# DE-100224_01.net
KiCad netlist of a schematic drawn in Altium Designer
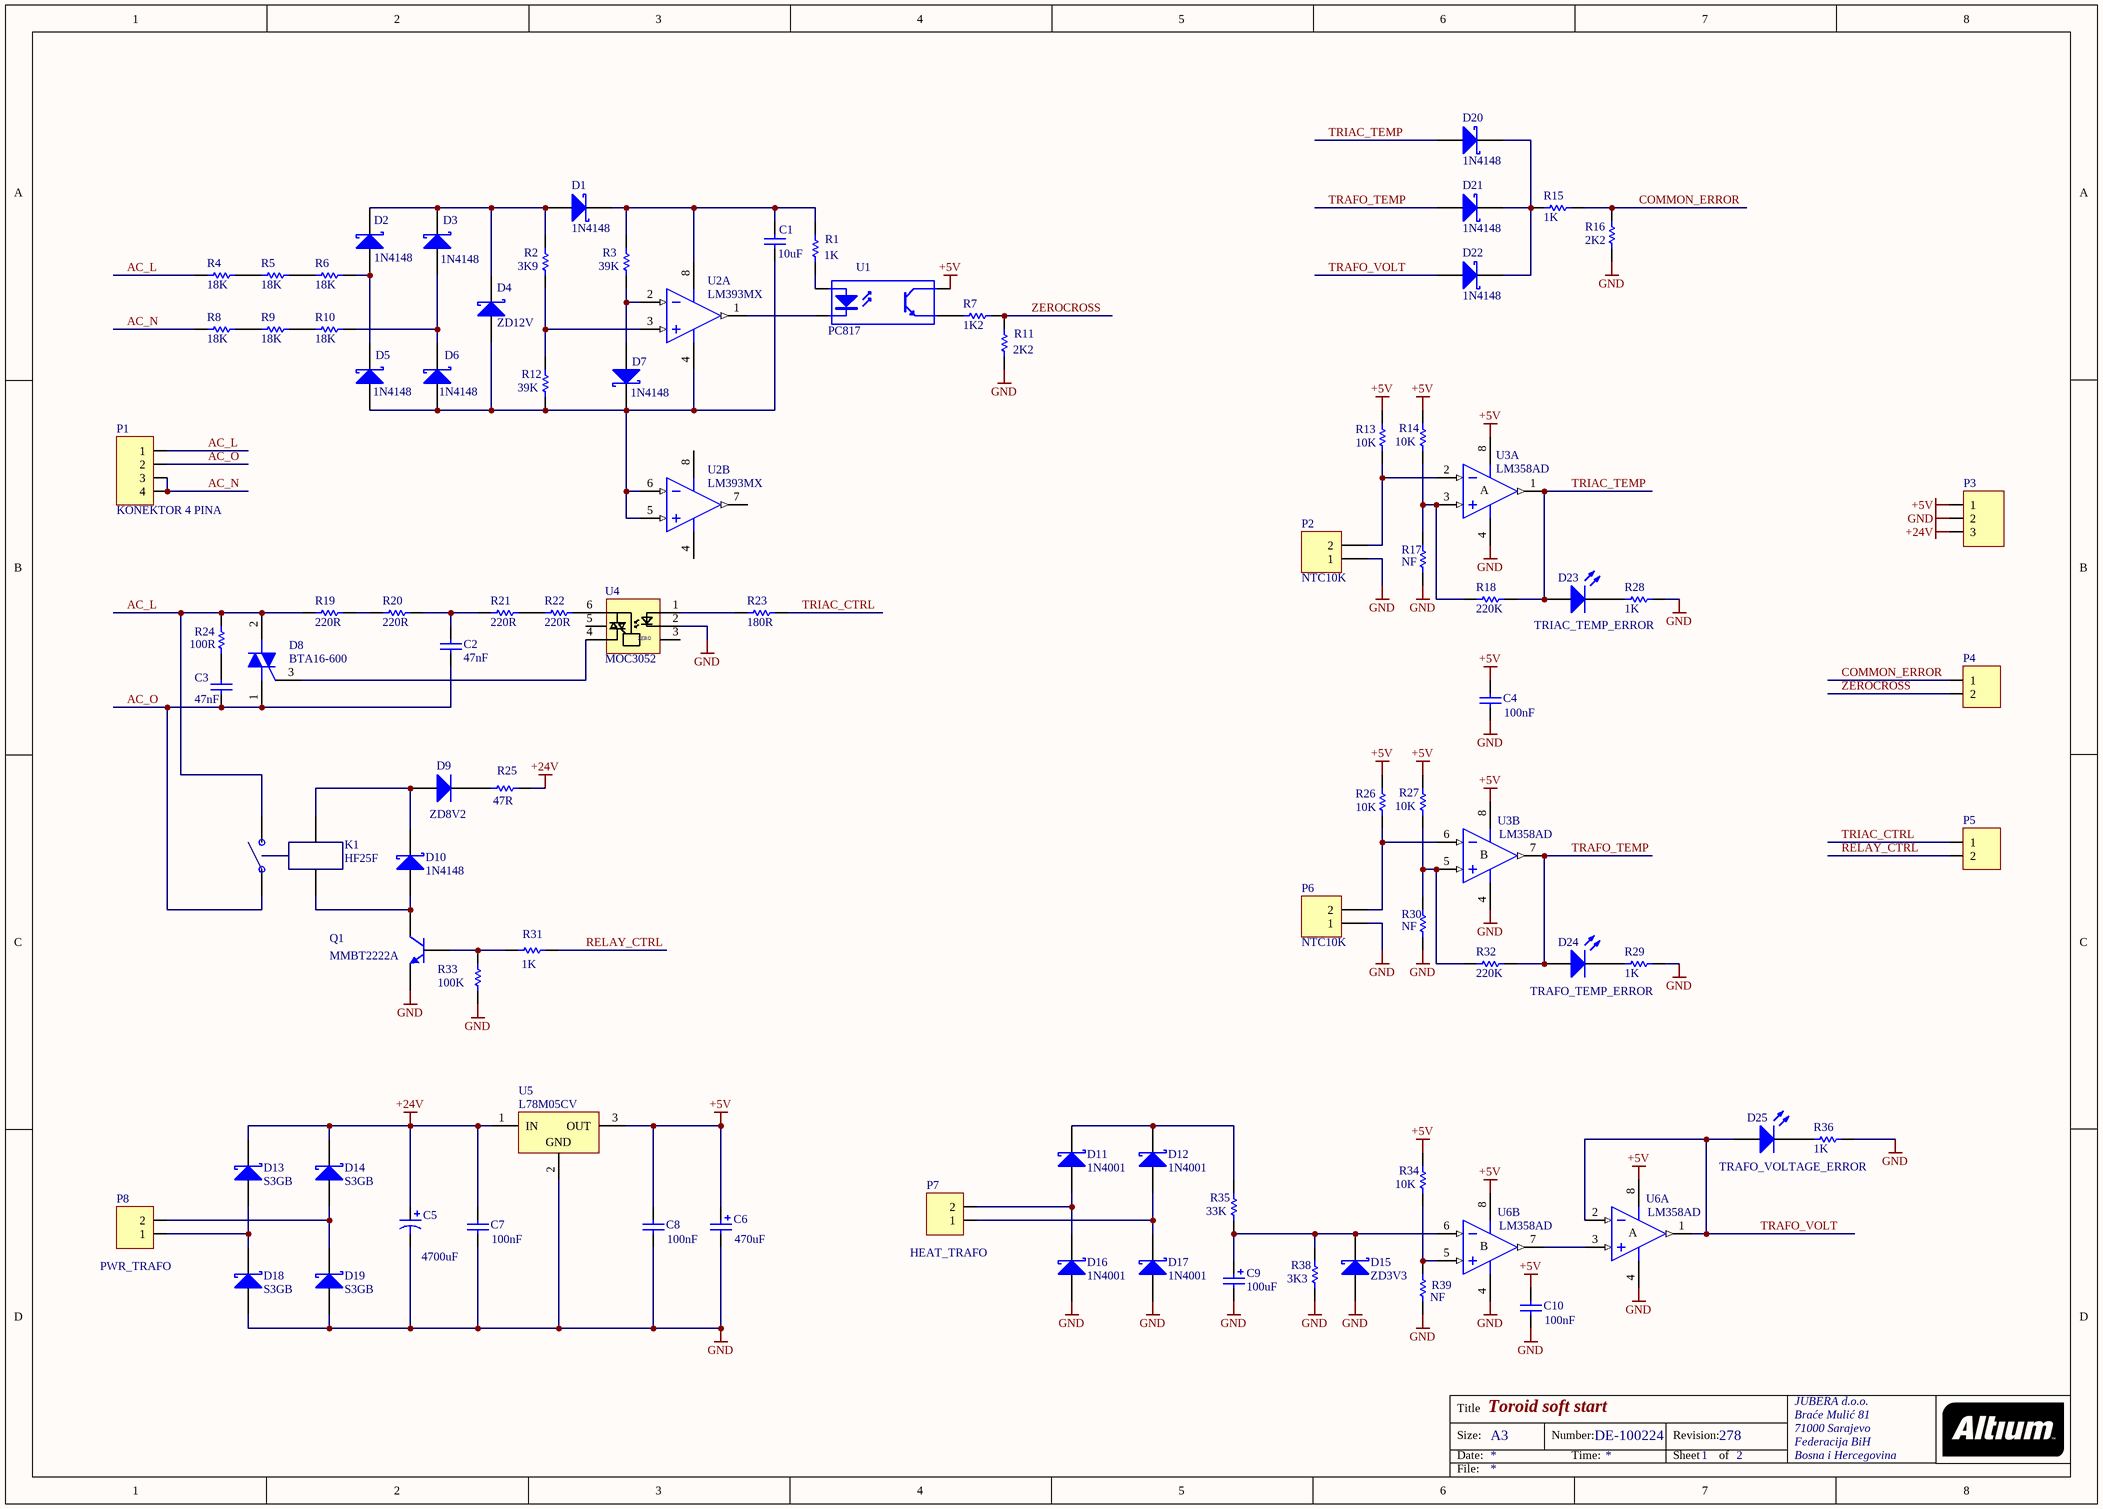
[diagram p0: DE-100224_01.SchDoc]

(export (version "E")
  (design (tool "Eeschema 10.0.6"))
  (components
    (comp (ref "C1")
      (value "10uF")
      (footprint "0805")
      (description "Ceramic Chip Capacitor - Standard")
      (fields (field (name "PUBLISHER") "Altium Limited"))
      (libsource (lib "DE-100224") (part "C0805"))
    )
    (comp (ref "C2")
      (value "47nF")
      (footprint "X2 CAP")
      (description "X2 275VAC capaitor")
      (libsource (lib "DE-100224") (part "CAP X2"))
    )
    (comp (ref "C3")
      (value "47nF")
      (footprint "X2 CAP")
      (description "X2 275VAC capaitor")
      (libsource (lib "DE-100224") (part "CAP X2"))
    )
    (comp (ref "C4")
      (value "100nF")
      (footprint "0603")
      (description "Ceramic Chip Capacitor - Standard")
      (fields (field (name "PUBLISHER") "Altium Limited"))
      (libsource (lib "DE-100224") (part "C0603"))
    )
    (comp (ref "C5")
      (value "4700uF")
      (footprint "CAPPR5-13X25")
      (description "Aluminum Electrolytic Capacitor, Radial Style with Long Leads: 4700uF, 10V")
      (fields (field (name "PUBLISHER") "Altium Limited"))
      (libsource (lib "Vishay Roederstein Electrolytic Radial-Lead Capacitor") (part "EKA00GG447C00"))
    )
    (comp (ref "C6")
      (value "470uF")
      (footprint "CAPPR5-10X16")
      (description "Aluminum Electrolytic Capacitor, Radial Style with Long Leads: 470uF, 35V")
      (fields (field (name "PUBLISHER") "Altium Limited"))
      (libsource (lib "DE-100224") (part "EKA00DD347F00"))
    )
    (comp (ref "C7")
      (value "100nF")
      (footprint "0603")
      (description "Ceramic Chip Capacitor - Standard")
      (fields (field (name "PUBLISHER") "Altium Limited"))
      (libsource (lib "DE-100224") (part "C0603"))
    )
    (comp (ref "C8")
      (value "100nF")
      (footprint "0603")
      (description "Ceramic Chip Capacitor - Standard")
      (fields (field (name "PUBLISHER") "Altium Limited"))
      (libsource (lib "DE-100224") (part "C0603"))
    )
    (comp (ref "C9")
      (value "100uF")
      (footprint "CAPPR2-5X11")
      (description "Aluminum Electrolytic Capacitor, Radial Style with Long Leads: 47uF, 35V")
      (fields (field (name "PUBLISHER") "Altium Limited"))
      (libsource (lib "DE-100224") (part "EKA00AA247F00"))
    )
    (comp (ref "C10")
      (value "100nF")
      (footprint "0603")
      (description "Ceramic Chip Capacitor - Standard")
      (fields (field (name "PUBLISHER") "Altium Limited"))
      (libsource (lib "DE-100224") (part "C0603"))
    )
    (comp (ref "D1")
      (value "1N4148")
      (footprint "SOD323")
      (description "Schottky Barrier Diode")
      (fields (field (name "PUBLISHER") "Altium Limited"))
      (libsource (lib "DE-100224") (part "1PS76SB10"))
    )
    (comp (ref "D2")
      (value "1N4148")
      (footprint "SOD323")
      (description "Schottky Barrier Diode")
      (fields (field (name "PUBLISHER") "Altium Limited"))
      (libsource (lib "DE-100224") (part "1PS76SB10"))
    )
    (comp (ref "D3")
      (value "1N4148")
      (footprint "SOD323")
      (description "Schottky Barrier Diode")
      (fields (field (name "PUBLISHER") "Altium Limited"))
      (libsource (lib "DE-100224") (part "1PS76SB10"))
    )
    (comp (ref "D4")
      (value "ZD12V")
      (footprint "SMB")
      (description "Schottky Rectifier")
      (fields (field (name "PUBLISHER") "Altium Limited"))
      (libsource (lib "DE-100224") (part "10BQ100"))
    )
    (comp (ref "D5")
      (value "1N4148")
      (footprint "SOD323")
      (description "Schottky Barrier Diode")
      (fields (field (name "PUBLISHER") "Altium Limited"))
      (libsource (lib "DE-100224") (part "1PS76SB10"))
    )
    (comp (ref "D6")
      (value "1N4148")
      (footprint "SOD323")
      (description "Schottky Barrier Diode")
      (fields (field (name "PUBLISHER") "Altium Limited"))
      (libsource (lib "DE-100224") (part "1PS76SB10"))
    )
    (comp (ref "D7")
      (value "1N4148")
      (footprint "SOD323")
      (description "Schottky Barrier Diode")
      (fields (field (name "PUBLISHER") "Altium Limited"))
      (libsource (lib "DE-100224") (part "1PS76SB10"))
    )
    (comp (ref "D8")
      (value "BTA16-600")
      (footprint "ONSC-TO-220-3-221A-07")
      (description "Triacs, Silicon Bidirectional Thyristor, 3-Pin TO-220, Pb-Free, Tube")
      (fields (field (name "MANUFACTURER") "On Semiconductor") (field (name "PARTNUMBER") "BTA08-600BW3G"))
      (libsource (lib "DE-100224") (part "BTA08-600BW3G"))
    )
    (comp (ref "D9")
      (value "ZD8V2")
      (footprint "DO-41")
      (description "1.0 Ampere General Purpose Rectifier")
      (fields (field (name "PUBLISHER") "Altium Limited"))
      (libsource (lib "DE-100224") (part "1N4003"))
    )
    (comp (ref "D10")
      (value "1N4148")
      (footprint "SOD323")
      (description "Schottky Barrier Diode")
      (fields (field (name "PUBLISHER") "Altium Limited"))
      (libsource (lib "DE-100224") (part "1PS76SB10"))
    )
    (comp (ref "D11")
      (value "1N4001")
      (footprint "SMB")
      (description "Schottky Diode")
      (fields (field (name "PUBLISHER") "Altium Limited"))
      (libsource (lib "Miscellaneous Devices") (part "D Schottky"))
    )
    (comp (ref "D12")
      (value "1N4001")
      (footprint "SMB")
      (description "Schottky Diode")
      (fields (field (name "PUBLISHER") "Altium Limited"))
      (libsource (lib "Miscellaneous Devices") (part "D Schottky"))
    )
    (comp (ref "D13")
      (value "S3GB")
      (footprint "SMB")
      (description "Schottky Diode")
      (fields (field (name "PUBLISHER") "Altium Limited"))
      (libsource (lib "Miscellaneous Devices") (part "D Schottky"))
    )
    (comp (ref "D14")
      (value "S3GB")
      (footprint "SMB")
      (description "Schottky Diode")
      (fields (field (name "PUBLISHER") "Altium Limited"))
      (libsource (lib "Miscellaneous Devices") (part "D Schottky"))
    )
    (comp (ref "D15")
      (value "ZD3V3")
      (footprint "SOD323")
      (description "Schottky Barrier Diode")
      (fields (field (name "PUBLISHER") "Altium Limited"))
      (libsource (lib "DE-100224") (part "1PS76SB10"))
    )
    (comp (ref "D16")
      (value "1N4001")
      (footprint "SMB")
      (description "Schottky Diode")
      (fields (field (name "PUBLISHER") "Altium Limited"))
      (libsource (lib "Miscellaneous Devices") (part "D Schottky"))
    )
    (comp (ref "D17")
      (value "1N4001")
      (footprint "SMB")
      (description "Schottky Diode")
      (fields (field (name "PUBLISHER") "Altium Limited"))
      (libsource (lib "Miscellaneous Devices") (part "D Schottky"))
    )
    (comp (ref "D18")
      (value "S3GB")
      (footprint "SMB")
      (description "Schottky Diode")
      (fields (field (name "PUBLISHER") "Altium Limited"))
      (libsource (lib "Miscellaneous Devices") (part "D Schottky"))
    )
    (comp (ref "D19")
      (value "S3GB")
      (footprint "SMB")
      (description "Schottky Diode")
      (fields (field (name "PUBLISHER") "Altium Limited"))
      (libsource (lib "Miscellaneous Devices") (part "D Schottky"))
    )
    (comp (ref "D20")
      (value "1N4148")
      (footprint "SOD323")
      (description "Schottky Barrier Diode")
      (fields (field (name "PUBLISHER") "Altium Limited"))
      (libsource (lib "DE-100224") (part "1PS76SB10"))
    )
    (comp (ref "D21")
      (value "1N4148")
      (footprint "SOD323")
      (description "Schottky Barrier Diode")
      (fields (field (name "PUBLISHER") "Altium Limited"))
      (libsource (lib "DE-100224") (part "1PS76SB10"))
    )
    (comp (ref "D22")
      (value "1N4148")
      (footprint "SOD323")
      (description "Schottky Barrier Diode")
      (fields (field (name "PUBLISHER") "Altium Limited"))
      (libsource (lib "DE-100224") (part "1PS76SB10"))
    )
    (comp (ref "D23")
      (value "TRIAC_TEMP_ERROR")
      (footprint "1.6X0.8X0.8")
      (description "Blue Surface Mount Chip LED, Blue")
      (fields (field (name "PUBLISHER") "Altium Limited"))
      (libsource (lib "DE-100224") (part "HSMB-C190"))
    )
    (comp (ref "D24")
      (value "TRAFO_TEMP_ERROR")
      (footprint "1.6X0.8X0.8")
      (description "Blue Surface Mount Chip LED, Blue")
      (fields (field (name "PUBLISHER") "Altium Limited"))
      (libsource (lib "DE-100224") (part "HSMB-C190"))
    )
    (comp (ref "D25")
      (value "TRAFO_VOLTAGE_ERROR")
      (footprint "1.6X0.8X0.8")
      (description "Blue Surface Mount Chip LED, Blue")
      (fields (field (name "PUBLISHER") "Altium Limited"))
      (libsource (lib "DE-100224") (part "HSMB-C190"))
    )
    (comp (ref "K1")
      (value "HF25F")
      (footprint "HF25F")
      (description "PCB relay 250VAC/20A 30VDC/16A")
      (libsource (lib "DE-100224") (part "HF25F"))
    )
    (comp (ref "P1")
      (value "KONEKTOR 4 PINA")
      (footprint "KONEKTOR 4 PINA")
      (description "Razdvojivi konektor 4 pina")
      (libsource (lib "DE-100224") (part "KONEKTOR 4 PINA"))
    )
    (comp (ref "P2")
      (value "NTC10K")
      (footprint "HDR1X2")
      (description "Header, 2-Pin")
      (fields (field (name "PUBLISHER") "Altium Limited"))
      (libsource (lib "Miscellaneous Connectors") (part "Header 2"))
    )
    (comp (ref "P3")
      (value "~")
      (footprint "TERMINAL BLOK 3")
      (description "3 pinski terminal blok konektor")
      (libsource (lib "DE-100224") (part "TERMINAL BLOK 3"))
    )
    (comp (ref "P4")
      (value "~")
      (footprint "TERMINAL BLOK 2")
      (description "Terminal blok konektor 3,5 mm")
      (libsource (lib "DE-100224") (part "TERMINAL BLOK 2"))
    )
    (comp (ref "P5")
      (value "~")
      (footprint "TERMINAL BLOK 2")
      (description "Terminal blok konektor 3,5 mm")
      (libsource (lib "DE-100224") (part "TERMINAL BLOK 2"))
    )
    (comp (ref "P6")
      (value "NTC10K")
      (footprint "HDR1X2")
      (description "Header, 2-Pin")
      (fields (field (name "PUBLISHER") "Altium Limited"))
      (libsource (lib "Miscellaneous Connectors") (part "Header 2"))
    )
    (comp (ref "P7")
      (value "HEAT_TRAFO")
      (footprint "KONEKTOR 2 PINA")
      (description "Razdvojivi konetor 2 pina")
      (libsource (lib "DE-100224") (part "KONEKTOR 2 PINA"))
    )
    (comp (ref "P8")
      (value "PWR_TRAFO")
      (footprint "KONEKTOR 2 PINA")
      (description "Razdvojivi konetor 2 pina")
      (libsource (lib "DE-100224") (part "KONEKTOR 2 PINA"))
    )
    (comp (ref "Q1")
      (value "MMBT2222A")
      (footprint "SOT23_N")
      (description "NPN General-purpose Transistor")
      (fields (field (name "PUBLISHER") "Altium Limited"))
      (libsource (lib "DE-100224") (part "BC817"))
    )
    (comp (ref "R1")
      (value "1K")
      (footprint "ERA-0603")
      (fields (field (name "PUBLISHER") "Altium Limited"))
      (libsource (lib "DE-100224") (part "ERAV"))
    )
    (comp (ref "R2")
      (value "3K9")
      (footprint "ERA-0603")
      (fields (field (name "PUBLISHER") "Altium Limited"))
      (libsource (lib "DE-100224") (part "ERAV"))
    )
    (comp (ref "R3")
      (value "39K")
      (footprint "ERA-0603")
      (fields (field (name "PUBLISHER") "Altium Limited"))
      (libsource (lib "DE-100224") (part "ERAV"))
    )
    (comp (ref "R4")
      (value "18K")
      (footprint "ERA-0805")
      (fields (field (name "PUBLISHER") "Altium Limited"))
      (libsource (lib "DE-100224") (part "ERAS"))
    )
    (comp (ref "R5")
      (value "18K")
      (footprint "ERA-0805")
      (fields (field (name "PUBLISHER") "Altium Limited"))
      (libsource (lib "DE-100224") (part "ERAS"))
    )
    (comp (ref "R6")
      (value "18K")
      (footprint "ERA-0805")
      (fields (field (name "PUBLISHER") "Altium Limited"))
      (libsource (lib "DE-100224") (part "ERAS"))
    )
    (comp (ref "R7")
      (value "1K2")
      (footprint "ERA-0603")
      (fields (field (name "PUBLISHER") "Altium Limited"))
      (libsource (lib "DE-100224") (part "ERAV"))
    )
    (comp (ref "R8")
      (value "18K")
      (footprint "ERA-0805")
      (fields (field (name "PUBLISHER") "Altium Limited"))
      (libsource (lib "DE-100224") (part "ERAS"))
    )
    (comp (ref "R9")
      (value "18K")
      (footprint "ERA-0805")
      (fields (field (name "PUBLISHER") "Altium Limited"))
      (libsource (lib "DE-100224") (part "ERAS"))
    )
    (comp (ref "R10")
      (value "18K")
      (footprint "ERA-0805")
      (fields (field (name "PUBLISHER") "Altium Limited"))
      (libsource (lib "DE-100224") (part "ERAS"))
    )
    (comp (ref "R11")
      (value "2K2")
      (footprint "ERA-0603")
      (fields (field (name "PUBLISHER") "Altium Limited"))
      (libsource (lib "DE-100224") (part "ERAV"))
    )
    (comp (ref "R12")
      (value "39K")
      (footprint "ERA-0603")
      (fields (field (name "PUBLISHER") "Altium Limited"))
      (libsource (lib "DE-100224") (part "ERAV"))
    )
    (comp (ref "R13")
      (value "10K")
      (footprint "ERA-0603")
      (fields (field (name "PUBLISHER") "Altium Limited"))
      (libsource (lib "DE-100224") (part "ERAV"))
    )
    (comp (ref "R14")
      (value "10K")
      (footprint "ERA-0603")
      (fields (field (name "PUBLISHER") "Altium Limited"))
      (libsource (lib "DE-100224") (part "ERAV"))
    )
    (comp (ref "R15")
      (value "1K")
      (footprint "ERA-0603")
      (fields (field (name "PUBLISHER") "Altium Limited"))
      (libsource (lib "DE-100224") (part "ERAV"))
    )
    (comp (ref "R16")
      (value "2K2")
      (footprint "ERA-0603")
      (fields (field (name "PUBLISHER") "Altium Limited"))
      (libsource (lib "DE-100224") (part "ERAV"))
    )
    (comp (ref "R17")
      (value "NF")
      (footprint "ERA-0603")
      (fields (field (name "PUBLISHER") "Altium Limited"))
      (libsource (lib "DE-100224") (part "ERAV"))
    )
    (comp (ref "R18")
      (value "220K")
      (footprint "ERA-0603")
      (fields (field (name "PUBLISHER") "Altium Limited"))
      (libsource (lib "DE-100224") (part "ERAV"))
    )
    (comp (ref "R19")
      (value "220R")
      (footprint "ERA-0805")
      (fields (field (name "PUBLISHER") "Altium Limited"))
      (libsource (lib "DE-100224") (part "ERAS"))
    )
    (comp (ref "R20")
      (value "220R")
      (footprint "ERA-0805")
      (fields (field (name "PUBLISHER") "Altium Limited"))
      (libsource (lib "DE-100224") (part "ERAS"))
    )
    (comp (ref "R21")
      (value "220R")
      (footprint "ERA-0805")
      (fields (field (name "PUBLISHER") "Altium Limited"))
      (libsource (lib "DE-100224") (part "ERAS"))
    )
    (comp (ref "R22")
      (value "220R")
      (footprint "ERA-0805")
      (fields (field (name "PUBLISHER") "Altium Limited"))
      (libsource (lib "DE-100224") (part "ERAS"))
    )
    (comp (ref "R23")
      (value "180R")
      (footprint "ERA-0603")
      (fields (field (name "PUBLISHER") "Altium Limited"))
      (libsource (lib "DE-100224") (part "ERAV"))
    )
    (comp (ref "R24")
      (value "100R")
      (footprint "1W100R")
      (description "Carbon F 1W resistor")
      (fields (field (name "PUBLISHER") "Altium Limited"))
      (libsource (lib "DE-100224") (part "1W100R"))
    )
    (comp (ref "R25")
      (value "47R")
      (footprint "AXIAL-0.3")
      (description "Resistor")
      (fields (field (name "Comment") "Res1") (field (name "PUBLISHER") "Altium Limited"))
      (libsource (lib "Miscellaneous Devices") (part "Res1"))
    )
    (comp (ref "R26")
      (value "10K")
      (footprint "ERA-0603")
      (fields (field (name "PUBLISHER") "Altium Limited"))
      (libsource (lib "DE-100224") (part "ERAV"))
    )
    (comp (ref "R27")
      (value "10K")
      (footprint "ERA-0603")
      (fields (field (name "PUBLISHER") "Altium Limited"))
      (libsource (lib "DE-100224") (part "ERAV"))
    )
    (comp (ref "R28")
      (value "1K")
      (footprint "ERA-0603")
      (fields (field (name "PUBLISHER") "Altium Limited"))
      (libsource (lib "DE-100224") (part "ERAV"))
    )
    (comp (ref "R29")
      (value "1K")
      (footprint "ERA-0603")
      (fields (field (name "PUBLISHER") "Altium Limited"))
      (libsource (lib "DE-100224") (part "ERAV"))
    )
    (comp (ref "R30")
      (value "NF")
      (footprint "ERA-0603")
      (fields (field (name "PUBLISHER") "Altium Limited"))
      (libsource (lib "DE-100224") (part "ERAV"))
    )
    (comp (ref "R31")
      (value "1K")
      (footprint "ERA-0603")
      (fields (field (name "PUBLISHER") "Altium Limited"))
      (libsource (lib "DE-100224") (part "ERAV"))
    )
    (comp (ref "R32")
      (value "220K")
      (footprint "ERA-0603")
      (fields (field (name "PUBLISHER") "Altium Limited"))
      (libsource (lib "DE-100224") (part "ERAV"))
    )
    (comp (ref "R33")
      (value "100K")
      (footprint "ERA-0603")
      (fields (field (name "PUBLISHER") "Altium Limited"))
      (libsource (lib "DE-100224") (part "ERAV"))
    )
    (comp (ref "R34")
      (value "10K")
      (footprint "ERA-0603")
      (fields (field (name "PUBLISHER") "Altium Limited"))
      (libsource (lib "DE-100224") (part "ERAV"))
    )
    (comp (ref "R35")
      (value "33K")
      (footprint "ERA-0603")
      (fields (field (name "PUBLISHER") "Altium Limited"))
      (libsource (lib "DE-100224") (part "ERAV"))
    )
    (comp (ref "R36")
      (value "1K")
      (footprint "ERA-0603")
      (fields (field (name "PUBLISHER") "Altium Limited"))
      (libsource (lib "DE-100224") (part "ERAV"))
    )
    (comp (ref "R38")
      (value "3K3")
      (footprint "ERA-0603")
      (fields (field (name "PUBLISHER") "Altium Limited"))
      (libsource (lib "DE-100224") (part "ERAV"))
    )
    (comp (ref "R39")
      (value "NF")
      (footprint "ERA-0603")
      (fields (field (name "PUBLISHER") "Altium Limited"))
      (libsource (lib "DE-100224") (part "ERAV"))
    )
    (comp (ref "U1")
      (value "PC817")
      (footprint "DIP-4")
      (description "4-Pin Phototransistor Optocoupler")
      (fields (field (name "PUBLISHER") "Altium Limited"))
      (libsource (lib "DE-100224") (part "PC817"))
    )
    (comp (ref "U2")
      (value "LM393MX")
      (footprint "M08A_N")
      (description "Low Power Low Offset Voltage Dual Comparator, 8-pin Narrow SOIC")
      (fields (field (name "MANUFACTURER") "National Semiconductor"))
      (libsource (lib "National Semiconductor Comparator") (part "LM393MX"))
    )
    (comp (ref "U3")
      (value "LM358AD")
      (footprint "SO8_N")
      (description "Low-Power Dual Operational Amplifier")
      (fields (field (name "PUBLISHER") "Altium Limited"))
      (libsource (lib "ST Operational Amplifier") (part "LM358AD"))
    )
    (comp (ref "U4")
      (value "MOC3052")
      (footprint "DIP6")
      (description "Zero-Cross Optoisolator Triac Driver")
      (libsource (lib "DE-100224") (part "MOC3081"))
    )
    (comp (ref "U5")
      (value "L78M05CV")
      (footprint "TO220")
      (description "Positive Voltage Regulator, 5V, 3-Pin TO-220")
      (libsource (lib "STMicroelectronics Power Management Linear Regulator") (part "L78M05CV"))
    )
    (comp (ref "U6")
      (value "LM358AD")
      (footprint "SO8_N")
      (description "Low-Power Dual Operational Amplifier")
      (fields (field (name "PUBLISHER") "Altium Limited"))
      (libsource (lib "ST Operational Amplifier") (part "LM358AD"))
    )
  )
  (nets
    (net (code "1") (name "+5V") (class "Default")
      (node (ref "C10") (pin "2") (pinfunction "2_2") (pintype "passive"))
      (node (ref "C4") (pin "2") (pinfunction "2_2") (pintype "passive"))
      (node (ref "C6") (pin "1") (pinfunction "1_1") (pintype "passive"))
      (node (ref "C8") (pin "2") (pinfunction "2_2") (pintype "passive"))
      (node (ref "P3") (pin "1") (pinfunction "1_1") (pintype "passive"))
      (node (ref "R13") (pin "2") (pinfunction "2_2") (pintype "passive"))
      (node (ref "R14") (pin "2") (pinfunction "2_2") (pintype "passive"))
      (node (ref "R26") (pin "2") (pinfunction "2_2") (pintype "passive"))
      (node (ref "R27") (pin "2") (pinfunction "2_2") (pintype "passive"))
      (node (ref "R34") (pin "2") (pinfunction "2_2") (pintype "passive"))
      (node (ref "U1") (pin "4") (pinfunction "C_4") (pintype "passive"))
      (node (ref "U3") (pin "8") (pinfunction "V+_8") (pintype "power_in"))
      (node (ref "U5") (pin "3") (pinfunction "OUT_3") (pintype "power_in"))
      (node (ref "U6") (pin "8") (pinfunction "V+_8") (pintype "power_in"))
    )
    (net (code "2") (name "+24V") (class "Default")
      (node (ref "C5") (pin "1") (pinfunction "1_1") (pintype "passive"))
      (node (ref "C7") (pin "2") (pinfunction "2_2") (pintype "passive"))
      (node (ref "D13") (pin "2") (pinfunction "K_2") (pintype "passive"))
      (node (ref "D14") (pin "2") (pinfunction "K_2") (pintype "passive"))
      (node (ref "P3") (pin "3") (pinfunction "3_3") (pintype "passive"))
      (node (ref "R25") (pin "2") (pinfunction "2_2") (pintype "passive"))
      (node (ref "U5") (pin "1") (pinfunction "IN_1") (pintype "power_in"))
    )
    (net (code "3") (name "/AC_L") (class "Default")
      (node (ref "D8") (pin "2") (pinfunction "MT2_2") (pintype "passive"))
      (node (ref "K1") (pin "4") (pinfunction "4_4") (pintype "passive"))
      (node (ref "P1") (pin "1") (pinfunction "1_1") (pintype "passive"))
      (node (ref "R19") (pin "1") (pinfunction "1_1") (pintype "passive"))
      (node (ref "R24") (pin "2") (pinfunction "2_2") (pintype "passive"))
      (node (ref "R4") (pin "1") (pinfunction "1_1") (pintype "passive"))
    )
    (net (code "4") (name "/AC_N") (class "Default")
      (node (ref "P1") (pin "3") (pinfunction "3_3") (pintype "passive"))
      (node (ref "P1") (pin "4") (pinfunction "4_4") (pintype "passive"))
      (node (ref "R8") (pin "1") (pinfunction "1_1") (pintype "passive"))
    )
    (net (code "5") (name "/AC_O") (class "Default")
      (node (ref "C2") (pin "1") (pinfunction "1_1") (pintype "passive"))
      (node (ref "C3") (pin "1") (pinfunction "1_1") (pintype "passive"))
      (node (ref "D8") (pin "1") (pinfunction "MT1_1") (pintype "passive"))
      (node (ref "K1") (pin "3") (pinfunction "3_3") (pintype "passive"))
      (node (ref "P1") (pin "2") (pinfunction "2_2") (pintype "passive"))
    )
    (net (code "6") (name "/COMMON_ERROR") (class "Default")
      (node (ref "P4") (pin "1") (pinfunction "1_1") (pintype "passive"))
      (node (ref "R15") (pin "1") (pinfunction "1_1") (pintype "passive"))
      (node (ref "R16") (pin "2") (pinfunction "2_2") (pintype "passive"))
    )
    (net (code "7") (name "/RELAY_CTRL") (class "Default")
      (node (ref "P5") (pin "2") (pinfunction "2_2") (pintype "passive"))
      (node (ref "R31") (pin "1") (pinfunction "1_1") (pintype "passive"))
    )
    (net (code "8") (name "/TRAFO_TEMP") (class "Default")
      (node (ref "D21") (pin "2") (pinfunction "A_2") (pintype "passive"))
      (node (ref "D24") (pin "1") (pinfunction "A_1") (pintype "passive"))
      (node (ref "R32") (pin "1") (pinfunction "1_1") (pintype "passive"))
      (node (ref "U3") (pin "7") (pinfunction "OUT_7") (pintype "output"))
    )
    (net (code "9") (name "/TRAFO_VOLT") (class "Default")
      (node (ref "D22") (pin "2") (pinfunction "A_2") (pintype "passive"))
      (node (ref "D25") (pin "1") (pinfunction "A_1") (pintype "passive"))
      (node (ref "U6") (pin "1") (pinfunction "OUT_1") (pintype "output"))
      (node (ref "U6") (pin "2") (pinfunction "IN-_2") (pintype "input"))
    )
    (net (code "10") (name "/TRIAC_CTRL") (class "Default")
      (node (ref "P5") (pin "1") (pinfunction "1_1") (pintype "passive"))
      (node (ref "R23") (pin "1") (pinfunction "1_1") (pintype "passive"))
    )
    (net (code "11") (name "/TRIAC_TEMP") (class "Default")
      (node (ref "D20") (pin "2") (pinfunction "A_2") (pintype "passive"))
      (node (ref "D23") (pin "1") (pinfunction "A_1") (pintype "passive"))
      (node (ref "R18") (pin "1") (pinfunction "1_1") (pintype "passive"))
      (node (ref "U3") (pin "1") (pinfunction "OUT_1") (pintype "output"))
    )
    (net (code "12") (name "/ZEROCROSS") (class "Default")
      (node (ref "P4") (pin "2") (pinfunction "2_2") (pintype "passive"))
      (node (ref "R11") (pin "2") (pinfunction "2_2") (pintype "passive"))
      (node (ref "R7") (pin "1") (pinfunction "1_1") (pintype "passive"))
    )
    (net (code "13") (name "GND") (class "Default")
      (node (ref "C10") (pin "1") (pinfunction "1_1") (pintype "passive"))
      (node (ref "C4") (pin "1") (pinfunction "1_1") (pintype "passive"))
      (node (ref "C5") (pin "2") (pinfunction "2_2") (pintype "passive"))
      (node (ref "C6") (pin "2") (pinfunction "2_2") (pintype "passive"))
      (node (ref "C7") (pin "1") (pinfunction "1_1") (pintype "passive"))
      (node (ref "C8") (pin "1") (pinfunction "1_1") (pintype "passive"))
      (node (ref "C9") (pin "2") (pinfunction "2_2") (pintype "passive"))
      (node (ref "D15") (pin "2") (pinfunction "A_2") (pintype "passive"))
      (node (ref "D16") (pin "1") (pinfunction "A_1") (pintype "passive"))
      (node (ref "D17") (pin "1") (pinfunction "A_1") (pintype "passive"))
      (node (ref "D18") (pin "1") (pinfunction "A_1") (pintype "passive"))
      (node (ref "D19") (pin "1") (pinfunction "A_1") (pintype "passive"))
      (node (ref "P2") (pin "1") (pinfunction "1_1") (pintype "passive"))
      (node (ref "P3") (pin "2") (pinfunction "2_2") (pintype "passive"))
      (node (ref "P6") (pin "1") (pinfunction "1_1") (pintype "passive"))
      (node (ref "Q1") (pin "2") (pinfunction "E_2") (pintype "passive"))
      (node (ref "R11") (pin "1") (pinfunction "1_1") (pintype "passive"))
      (node (ref "R16") (pin "1") (pinfunction "1_1") (pintype "passive"))
      (node (ref "R17") (pin "1") (pinfunction "1_1") (pintype "passive"))
      (node (ref "R28") (pin "1") (pinfunction "1_1") (pintype "passive"))
      (node (ref "R29") (pin "1") (pinfunction "1_1") (pintype "passive"))
      (node (ref "R30") (pin "1") (pinfunction "1_1") (pintype "passive"))
      (node (ref "R33") (pin "1") (pinfunction "1_1") (pintype "passive"))
      (node (ref "R36") (pin "1") (pinfunction "1_1") (pintype "passive"))
      (node (ref "R38") (pin "1") (pinfunction "1_1") (pintype "passive"))
      (node (ref "R39") (pin "1") (pinfunction "1_1") (pintype "passive"))
      (node (ref "U3") (pin "4") (pinfunction "V-_4") (pintype "power_in"))
      (node (ref "U4") (pin "2") (pinfunction "2_2") (pintype "passive"))
      (node (ref "U5") (pin "2") (pinfunction "GND_2") (pintype "power_in"))
      (node (ref "U6") (pin "4") (pinfunction "V-_4") (pintype "power_in"))
    )
    (net (code "14") (name "Net-(C2-Pad2)") (class "Default")
      (node (ref "C2") (pin "2") (pinfunction "2_2") (pintype "passive"))
      (node (ref "R20") (pin "2") (pinfunction "2_2") (pintype "passive"))
      (node (ref "R21") (pin "1") (pinfunction "1_1") (pintype "passive"))
    )
    (net (code "15") (name "Net-(C3-Pad2)") (class "Default")
      (node (ref "C3") (pin "2") (pinfunction "2_2") (pintype "passive"))
      (node (ref "R24") (pin "1") (pinfunction "1_1") (pintype "passive"))
    )
    (net (code "16") (name "Net-(D1-A)") (class "Default")
      (node (ref "D1") (pin "2") (pinfunction "A_2") (pintype "passive"))
      (node (ref "D2") (pin "1") (pinfunction "K_1") (pintype "passive"))
      (node (ref "D3") (pin "1") (pinfunction "K_1") (pintype "passive"))
      (node (ref "D4") (pin "2") (pinfunction "K_2") (pintype "passive"))
      (node (ref "R2") (pin "2") (pinfunction "2_2") (pintype "passive"))
    )
    (net (code "17") (name "Net-(D1-K)") (class "Default")
      (node (ref "C1") (pin "2") (pinfunction "2_2") (pintype "passive"))
      (node (ref "D1") (pin "1") (pinfunction "K_1") (pintype "passive"))
      (node (ref "R1") (pin "2") (pinfunction "2_2") (pintype "passive"))
      (node (ref "R3") (pin "2") (pinfunction "2_2") (pintype "passive"))
      (node (ref "U2") (pin "8") (pinfunction "V+_8") (pintype "power_in"))
    )
    (net (code "18") (name "Net-(D2-A)") (class "Default")
      (node (ref "D2") (pin "2") (pinfunction "A_2") (pintype "passive"))
      (node (ref "D5") (pin "1") (pinfunction "K_1") (pintype "passive"))
      (node (ref "R6") (pin "2") (pinfunction "2_2") (pintype "passive"))
    )
    (net (code "19") (name "Net-(D3-A)") (class "Default")
      (node (ref "D3") (pin "2") (pinfunction "A_2") (pintype "passive"))
      (node (ref "D6") (pin "1") (pinfunction "K_1") (pintype "passive"))
      (node (ref "R10") (pin "2") (pinfunction "2_2") (pintype "passive"))
    )
    (net (code "20") (name "Net-(D4-A)") (class "Default")
      (node (ref "C1") (pin "1") (pinfunction "1_1") (pintype "passive"))
      (node (ref "D4") (pin "1") (pinfunction "A_1") (pintype "passive"))
      (node (ref "D5") (pin "2") (pinfunction "A_2") (pintype "passive"))
      (node (ref "D6") (pin "2") (pinfunction "A_2") (pintype "passive"))
      (node (ref "D7") (pin "1") (pinfunction "K_1") (pintype "passive"))
      (node (ref "R12") (pin "1") (pinfunction "1_1") (pintype "passive"))
      (node (ref "U2") (pin "4") (pinfunction "GND_4") (pintype "power_in"))
      (node (ref "U2") (pin "5") (pinfunction "INB+_5") (pintype "input"))
      (node (ref "U2") (pin "6") (pinfunction "INB-_6") (pintype "input"))
    )
    (net (code "21") (name "Net-(D7-A)") (class "Default")
      (node (ref "D7") (pin "2") (pinfunction "A_2") (pintype "passive"))
      (node (ref "R3") (pin "1") (pinfunction "1_1") (pintype "passive"))
      (node (ref "U2") (pin "2") (pinfunction "INA-_2") (pintype "input"))
    )
    (net (code "22") (name "Net-(D8-G)") (class "Default")
      (node (ref "D8") (pin "3") (pinfunction "G_3") (pintype "passive"))
      (node (ref "U4") (pin "4") (pinfunction "4_4") (pintype "passive"))
    )
    (net (code "23") (name "Net-(D9-K)") (class "Default")
      (node (ref "D9") (pin "2") (pinfunction "K_2") (pintype "passive"))
      (node (ref "R25") (pin "1") (pinfunction "1_1") (pintype "passive"))
    )
    (net (code "24") (name "Net-(D10-A)") (class "Default")
      (node (ref "D10") (pin "2") (pinfunction "A_2") (pintype "passive"))
      (node (ref "K1") (pin "1") (pinfunction "1_1") (pintype "passive"))
      (node (ref "Q1") (pin "3") (pinfunction "C_3") (pintype "passive"))
    )
    (net (code "25") (name "Net-(D10-K)") (class "Default")
      (node (ref "D10") (pin "1") (pinfunction "K_1") (pintype "passive"))
      (node (ref "D9") (pin "1") (pinfunction "A_1") (pintype "passive"))
      (node (ref "K1") (pin "2") (pinfunction "2_2") (pintype "passive"))
    )
    (net (code "26") (name "Net-(D11-A)") (class "Default")
      (node (ref "D11") (pin "1") (pinfunction "A_1") (pintype "passive"))
      (node (ref "D16") (pin "2") (pinfunction "K_2") (pintype "passive"))
      (node (ref "P7") (pin "2") (pinfunction "2_2") (pintype "passive"))
    )
    (net (code "27") (name "Net-(D11-K)") (class "Default")
      (node (ref "D11") (pin "2") (pinfunction "K_2") (pintype "passive"))
      (node (ref "D12") (pin "2") (pinfunction "K_2") (pintype "passive"))
      (node (ref "R35") (pin "2") (pinfunction "2_2") (pintype "passive"))
    )
    (net (code "28") (name "Net-(D12-A)") (class "Default")
      (node (ref "D12") (pin "1") (pinfunction "A_1") (pintype "passive"))
      (node (ref "D17") (pin "2") (pinfunction "K_2") (pintype "passive"))
      (node (ref "P7") (pin "1") (pinfunction "1_1") (pintype "passive"))
    )
    (net (code "29") (name "Net-(D13-A)") (class "Default")
      (node (ref "D13") (pin "1") (pinfunction "A_1") (pintype "passive"))
      (node (ref "D18") (pin "2") (pinfunction "K_2") (pintype "passive"))
      (node (ref "P8") (pin "1") (pinfunction "1_1") (pintype "passive"))
    )
    (net (code "30") (name "Net-(D14-A)") (class "Default")
      (node (ref "D14") (pin "1") (pinfunction "A_1") (pintype "passive"))
      (node (ref "D19") (pin "2") (pinfunction "K_2") (pintype "passive"))
      (node (ref "P8") (pin "2") (pinfunction "2_2") (pintype "passive"))
    )
    (net (code "31") (name "Net-(D15-K)") (class "Default")
      (node (ref "C9") (pin "1") (pinfunction "1_1") (pintype "passive"))
      (node (ref "D15") (pin "1") (pinfunction "K_1") (pintype "passive"))
      (node (ref "R35") (pin "1") (pinfunction "1_1") (pintype "passive"))
      (node (ref "R38") (pin "2") (pinfunction "2_2") (pintype "passive"))
      (node (ref "U6") (pin "6") (pinfunction "IN-_6") (pintype "input"))
    )
    (net (code "32") (name "Net-(D20-K)") (class "Default")
      (node (ref "D20") (pin "1") (pinfunction "K_1") (pintype "passive"))
      (node (ref "D21") (pin "1") (pinfunction "K_1") (pintype "passive"))
      (node (ref "D22") (pin "1") (pinfunction "K_1") (pintype "passive"))
      (node (ref "R15") (pin "2") (pinfunction "2_2") (pintype "passive"))
    )
    (net (code "33") (name "Net-(D23-K)") (class "Default")
      (node (ref "D23") (pin "2") (pinfunction "K_2") (pintype "passive"))
      (node (ref "R28") (pin "2") (pinfunction "2_2") (pintype "passive"))
    )
    (net (code "34") (name "Net-(D24-K)") (class "Default")
      (node (ref "D24") (pin "2") (pinfunction "K_2") (pintype "passive"))
      (node (ref "R29") (pin "2") (pinfunction "2_2") (pintype "passive"))
    )
    (net (code "35") (name "Net-(D25-K)") (class "Default")
      (node (ref "D25") (pin "2") (pinfunction "K_2") (pintype "passive"))
      (node (ref "R36") (pin "2") (pinfunction "2_2") (pintype "passive"))
    )
    (net (code "36") (name "Net-(Q1-B)") (class "Default")
      (node (ref "Q1") (pin "1") (pinfunction "B_1") (pintype "passive"))
      (node (ref "R31") (pin "2") (pinfunction "2_2") (pintype "passive"))
      (node (ref "R33") (pin "2") (pinfunction "2_2") (pintype "passive"))
    )
    (net (code "37") (name "Net-(R4-Pad2)") (class "Default")
      (node (ref "R4") (pin "2") (pinfunction "2_2") (pintype "passive"))
      (node (ref "R5") (pin "1") (pinfunction "1_1") (pintype "passive"))
    )
    (net (code "38") (name "Net-(R5-Pad2)") (class "Default")
      (node (ref "R5") (pin "2") (pinfunction "2_2") (pintype "passive"))
      (node (ref "R6") (pin "1") (pinfunction "1_1") (pintype "passive"))
    )
    (net (code "39") (name "Net-(R8-Pad2)") (class "Default")
      (node (ref "R8") (pin "2") (pinfunction "2_2") (pintype "passive"))
      (node (ref "R9") (pin "1") (pinfunction "1_1") (pintype "passive"))
    )
    (net (code "40") (name "Net-(R10-Pad1)") (class "Default")
      (node (ref "R10") (pin "1") (pinfunction "1_1") (pintype "passive"))
      (node (ref "R9") (pin "2") (pinfunction "2_2") (pintype "passive"))
    )
    (net (code "41") (name "Net-(R19-Pad2)") (class "Default")
      (node (ref "R19") (pin "2") (pinfunction "2_2") (pintype "passive"))
      (node (ref "R20") (pin "1") (pinfunction "1_1") (pintype "passive"))
    )
    (net (code "42") (name "Net-(R21-Pad2)") (class "Default")
      (node (ref "R21") (pin "2") (pinfunction "2_2") (pintype "passive"))
      (node (ref "R22") (pin "1") (pinfunction "1_1") (pintype "passive"))
    )
    (net (code "43") (name "Net-(R22-Pad2)") (class "Default")
      (node (ref "R22") (pin "2") (pinfunction "2_2") (pintype "passive"))
      (node (ref "U4") (pin "6") (pinfunction "6_6") (pintype "passive"))
    )
    (net (code "44") (name "Net-(R23-Pad2)") (class "Default")
      (node (ref "R23") (pin "2") (pinfunction "2_2") (pintype "passive"))
      (node (ref "U4") (pin "1") (pinfunction "1_1") (pintype "passive"))
    )
    (net (code "45") (name "Net-(U1-A)") (class "Default")
      (node (ref "R1") (pin "1") (pinfunction "1_1") (pintype "passive"))
      (node (ref "U1") (pin "1") (pinfunction "A_1") (pintype "passive"))
    )
    (net (code "46") (name "Net-(U1-E)") (class "Default")
      (node (ref "R7") (pin "2") (pinfunction "2_2") (pintype "passive"))
      (node (ref "U1") (pin "3") (pinfunction "E_3") (pintype "passive"))
    )
    (net (code "47") (name "Net-(U1-K)") (class "Default")
      (node (ref "U1") (pin "2") (pinfunction "K_2") (pintype "passive"))
      (node (ref "U2") (pin "1") (pinfunction "OUTA_1") (pintype "output"))
    )
    (net (code "48") (name "Net-(U2A-INA+)") (class "Default")
      (node (ref "R12") (pin "2") (pinfunction "2_2") (pintype "passive"))
      (node (ref "R2") (pin "1") (pinfunction "1_1") (pintype "passive"))
      (node (ref "U2") (pin "3") (pinfunction "INA+_3") (pintype "input"))
    )
    (net (code "49") (name "Net-(U3A-IN+)") (class "Default")
      (node (ref "R14") (pin "1") (pinfunction "1_1") (pintype "passive"))
      (node (ref "R17") (pin "2") (pinfunction "2_2") (pintype "passive"))
      (node (ref "R18") (pin "2") (pinfunction "2_2") (pintype "passive"))
      (node (ref "U3") (pin "3") (pinfunction "IN+_3") (pintype "input"))
    )
    (net (code "50") (name "Net-(U3A-IN-)") (class "Default")
      (node (ref "P2") (pin "2") (pinfunction "2_2") (pintype "passive"))
      (node (ref "R13") (pin "1") (pinfunction "1_1") (pintype "passive"))
      (node (ref "U3") (pin "2") (pinfunction "IN-_2") (pintype "input"))
    )
    (net (code "51") (name "Net-(U3B-IN+)") (class "Default")
      (node (ref "R27") (pin "1") (pinfunction "1_1") (pintype "passive"))
      (node (ref "R30") (pin "2") (pinfunction "2_2") (pintype "passive"))
      (node (ref "R32") (pin "2") (pinfunction "2_2") (pintype "passive"))
      (node (ref "U3") (pin "5") (pinfunction "IN+_5") (pintype "input"))
    )
    (net (code "52") (name "Net-(U3B-IN-)") (class "Default")
      (node (ref "P6") (pin "2") (pinfunction "2_2") (pintype "passive"))
      (node (ref "R26") (pin "1") (pinfunction "1_1") (pintype "passive"))
      (node (ref "U3") (pin "6") (pinfunction "IN-_6") (pintype "input"))
    )
    (net (code "53") (name "Net-(U6A-IN+)") (class "Default")
      (node (ref "U6") (pin "3") (pinfunction "IN+_3") (pintype "input"))
      (node (ref "U6") (pin "7") (pinfunction "OUT_7") (pintype "output"))
    )
    (net (code "54") (name "Net-(U6B-IN+)") (class "Default")
      (node (ref "R34") (pin "1") (pinfunction "1_1") (pintype "passive"))
      (node (ref "R39") (pin "2") (pinfunction "2_2") (pintype "passive"))
      (node (ref "U6") (pin "5") (pinfunction "IN+_5") (pintype "input"))
    )
    (net (code "55") (name "unconnected-(U2B-GND-Pad4)") (class "Default")
      (node (ref "U2") (pin "4") (pinfunction "GND_4") (pintype "power_in"))
    )
    (net (code "56") (name "unconnected-(U2B-OUTB-Pad7)") (class "Default")
      (node (ref "U2") (pin "7") (pinfunction "OUTB_7") (pintype "output"))
    )
    (net (code "57") (name "unconnected-(U2B-V+-Pad8)") (class "Default")
      (node (ref "U2") (pin "8") (pinfunction "V+_8") (pintype "power_in"))
    )
    (net (code "58") (name "unconnected-(U4-Pad3)") (class "Default")
      (node (ref "U4") (pin "3") (pinfunction "3_3") (pintype "passive"))
    )
    (net (code "59") (name "unconnected-(U4-Pad5)") (class "Default")
      (node (ref "U4") (pin "5") (pinfunction "5_5") (pintype "passive"))
    )
  )
)
